# 001-0002_beaglebone_cape_board.net
KiCad netlist of a schematic drawn in Altium Designer
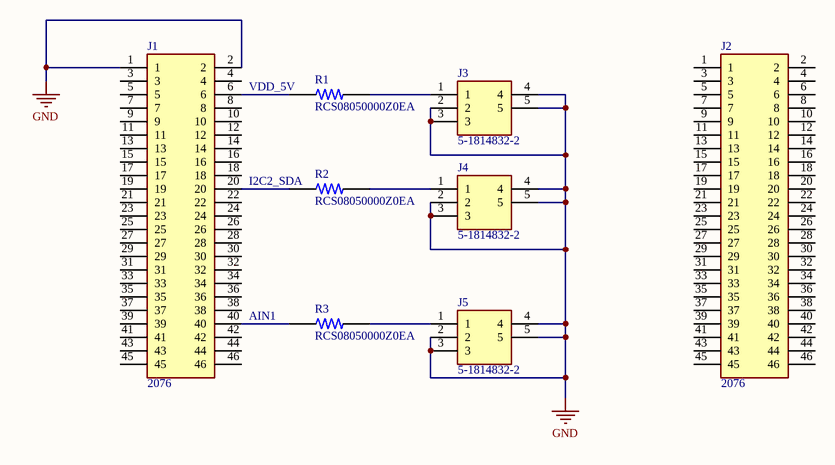
[diagram p0: 001-0002_beaglebone_cape_board.SchDoc]

(export (version "E")
  (design (tool "Eeschema 10.0.6"))
  (components
    (comp (ref "J1")
      (value "2076")
      (footprint "HDRV46W64P254_2X23_5842X500X874P")
      (description "Adafruit Accessories 2x23 Male Headers for BeagleBone Black - Two Pack")
      (fields (field (name "MOUSER PART NUMBER") "485-2076"))
      (libsource (lib "default") (part "2076"))
    )
    (comp (ref "J2")
      (value "2076")
      (footprint "HDRV46W64P254_2X23_5842X500X874P")
      (description "Adafruit Accessories 2x23 Male Headers for BeagleBone Black - Two Pack")
      (fields (field (name "MOUSER PART NUMBER") "485-2076"))
      (libsource (lib "default") (part "2076"))
    )
    (comp (ref "J3")
      (value "5-1814832-2")
      (footprint "5-1814832-2")
      (description "SMA Connector Jack, Female Socket 50 Ohms Through Hole Solder")
      (fields (field (name "MOUSER PART NUMBER") "571-5-1814832-2"))
      (libsource (lib "default") (part "5-1814832-2"))
    )
    (comp (ref "J4")
      (value "5-1814832-2")
      (footprint "5-1814832-2")
      (description "SMA Connector Jack, Female Socket 50 Ohms Through Hole Solder")
      (fields (field (name "MOUSER PART NUMBER") "571-5-1814832-2"))
      (libsource (lib "default") (part "5-1814832-2"))
    )
    (comp (ref "J5")
      (value "5-1814832-2")
      (footprint "5-1814832-2")
      (description "SMA Connector Jack, Female Socket 50 Ohms Through Hole Solder")
      (fields (field (name "MOUSER PART NUMBER") "571-5-1814832-2"))
      (libsource (lib "default") (part "5-1814832-2"))
    )
    (comp (ref "R1")
      (value "RCS08050000Z0EA")
      (footprint "default:RESC2012X50N")
      (description "RES SMD 0 OHM JUMPER 1/2W 0805")
      (fields (field (name "MF") "Vishay Dale") (field (name "DIGI-KEY_PART_NUMBER") "541-2827-1-ND"))
      (libsource (lib "default") (part "RCS08050000Z0EA"))
    )
    (comp (ref "R2")
      (value "RCS08050000Z0EA")
      (footprint "default:RESC2012X50N")
      (description "RES SMD 0 OHM JUMPER 1/2W 0805")
      (fields (field (name "MF") "Vishay Dale") (field (name "DIGI-KEY_PART_NUMBER") "541-2827-1-ND"))
      (libsource (lib "default") (part "RCS08050000Z0EA"))
    )
    (comp (ref "R3")
      (value "RCS08050000Z0EA")
      (footprint "default:RESC2012X50N")
      (description "RES SMD 0 OHM JUMPER 1/2W 0805")
      (fields (field (name "MF") "Vishay Dale") (field (name "DIGI-KEY_PART_NUMBER") "541-2827-1-ND"))
      (libsource (lib "default") (part "RCS08050000Z0EA"))
    )
  )
  (nets
    (net (code "1") (name "GND") (class "Default")
      (node (ref "J1") (pin "1") (pinfunction "1_1") (pintype "passive"))
      (node (ref "J1") (pin "2") (pinfunction "2_2") (pintype "passive"))
      (node (ref "J3") (pin "2") (pinfunction "2_2") (pintype "passive"))
      (node (ref "J3") (pin "3") (pinfunction "3_3") (pintype "passive"))
      (node (ref "J3") (pin "4") (pinfunction "4_4") (pintype "passive"))
      (node (ref "J3") (pin "5") (pinfunction "5_5") (pintype "passive"))
      (node (ref "J4") (pin "2") (pinfunction "2_2") (pintype "passive"))
      (node (ref "J4") (pin "3") (pinfunction "3_3") (pintype "passive"))
      (node (ref "J4") (pin "4") (pinfunction "4_4") (pintype "passive"))
      (node (ref "J4") (pin "5") (pinfunction "5_5") (pintype "passive"))
      (node (ref "J5") (pin "2") (pinfunction "2_2") (pintype "passive"))
      (node (ref "J5") (pin "3") (pinfunction "3_3") (pintype "passive"))
      (node (ref "J5") (pin "4") (pinfunction "4_4") (pintype "passive"))
      (node (ref "J5") (pin "5") (pinfunction "5_5") (pintype "passive"))
    )
    (net (code "2") (name "Net-(J1-Pad6)") (class "Default")
      (node (ref "J1") (pin "6") (pinfunction "6_6") (pintype "passive"))
      (node (ref "R1") (pin "1") (pinfunction "1_1") (pintype "passive"))
    )
    (net (code "3") (name "Net-(J1-Pad20)") (class "Default")
      (node (ref "J1") (pin "20") (pinfunction "20_20") (pintype "passive"))
      (node (ref "R2") (pin "1") (pinfunction "1_1") (pintype "passive"))
    )
    (net (code "4") (name "Net-(J1-Pad40)") (class "Default")
      (node (ref "J1") (pin "40") (pinfunction "40_40") (pintype "passive"))
      (node (ref "R3") (pin "1") (pinfunction "1_1") (pintype "passive"))
    )
    (net (code "5") (name "Net-(J3-Pad1)") (class "Default")
      (node (ref "J3") (pin "1") (pinfunction "1_1") (pintype "passive"))
      (node (ref "R1") (pin "2") (pinfunction "2_2") (pintype "passive"))
    )
    (net (code "6") (name "Net-(J4-Pad1)") (class "Default")
      (node (ref "J4") (pin "1") (pinfunction "1_1") (pintype "passive"))
      (node (ref "R2") (pin "2") (pinfunction "2_2") (pintype "passive"))
    )
    (net (code "7") (name "Net-(J5-Pad1)") (class "Default")
      (node (ref "J5") (pin "1") (pinfunction "1_1") (pintype "passive"))
      (node (ref "R3") (pin "2") (pinfunction "2_2") (pintype "passive"))
    )
    (net (code "8") (name "unconnected-(J1-Pad3)") (class "Default")
      (node (ref "J1") (pin "3") (pinfunction "3_3") (pintype "passive"))
    )
    (net (code "9") (name "unconnected-(J1-Pad4)") (class "Default")
      (node (ref "J1") (pin "4") (pinfunction "4_4") (pintype "passive"))
    )
    (net (code "10") (name "unconnected-(J1-Pad5)") (class "Default")
      (node (ref "J1") (pin "5") (pinfunction "5_5") (pintype "passive"))
    )
    (net (code "11") (name "unconnected-(J1-Pad7)") (class "Default")
      (node (ref "J1") (pin "7") (pinfunction "7_7") (pintype "passive"))
    )
    (net (code "12") (name "unconnected-(J1-Pad8)") (class "Default")
      (node (ref "J1") (pin "8") (pinfunction "8_8") (pintype "passive"))
    )
    (net (code "13") (name "unconnected-(J1-Pad9)") (class "Default")
      (node (ref "J1") (pin "9") (pinfunction "9_9") (pintype "passive"))
    )
    (net (code "14") (name "unconnected-(J1-Pad10)") (class "Default")
      (node (ref "J1") (pin "10") (pinfunction "10_10") (pintype "passive"))
    )
    (net (code "15") (name "unconnected-(J1-Pad11)") (class "Default")
      (node (ref "J1") (pin "11") (pinfunction "11_11") (pintype "passive"))
    )
    (net (code "16") (name "unconnected-(J1-Pad12)") (class "Default")
      (node (ref "J1") (pin "12") (pinfunction "12_12") (pintype "passive"))
    )
    (net (code "17") (name "unconnected-(J1-Pad13)") (class "Default")
      (node (ref "J1") (pin "13") (pinfunction "13_13") (pintype "passive"))
    )
    (net (code "18") (name "unconnected-(J1-Pad14)") (class "Default")
      (node (ref "J1") (pin "14") (pinfunction "14_14") (pintype "passive"))
    )
    (net (code "19") (name "unconnected-(J1-Pad15)") (class "Default")
      (node (ref "J1") (pin "15") (pinfunction "15_15") (pintype "passive"))
    )
    (net (code "20") (name "unconnected-(J1-Pad16)") (class "Default")
      (node (ref "J1") (pin "16") (pinfunction "16_16") (pintype "passive"))
    )
    (net (code "21") (name "unconnected-(J1-Pad17)") (class "Default")
      (node (ref "J1") (pin "17") (pinfunction "17_17") (pintype "passive"))
    )
    (net (code "22") (name "unconnected-(J1-Pad18)") (class "Default")
      (node (ref "J1") (pin "18") (pinfunction "18_18") (pintype "passive"))
    )
    (net (code "23") (name "unconnected-(J1-Pad19)") (class "Default")
      (node (ref "J1") (pin "19") (pinfunction "19_19") (pintype "passive"))
    )
    (net (code "24") (name "unconnected-(J1-Pad21)") (class "Default")
      (node (ref "J1") (pin "21") (pinfunction "21_21") (pintype "passive"))
    )
    (net (code "25") (name "unconnected-(J1-Pad22)") (class "Default")
      (node (ref "J1") (pin "22") (pinfunction "22_22") (pintype "passive"))
    )
    (net (code "26") (name "unconnected-(J1-Pad23)") (class "Default")
      (node (ref "J1") (pin "23") (pinfunction "23_23") (pintype "passive"))
    )
    (net (code "27") (name "unconnected-(J1-Pad24)") (class "Default")
      (node (ref "J1") (pin "24") (pinfunction "24_24") (pintype "passive"))
    )
    (net (code "28") (name "unconnected-(J1-Pad25)") (class "Default")
      (node (ref "J1") (pin "25") (pinfunction "25_25") (pintype "passive"))
    )
    (net (code "29") (name "unconnected-(J1-Pad26)") (class "Default")
      (node (ref "J1") (pin "26") (pinfunction "26_26") (pintype "passive"))
    )
    (net (code "30") (name "unconnected-(J1-Pad27)") (class "Default")
      (node (ref "J1") (pin "27") (pinfunction "27_27") (pintype "passive"))
    )
    (net (code "31") (name "unconnected-(J1-Pad28)") (class "Default")
      (node (ref "J1") (pin "28") (pinfunction "28_28") (pintype "passive"))
    )
    (net (code "32") (name "unconnected-(J1-Pad29)") (class "Default")
      (node (ref "J1") (pin "29") (pinfunction "29_29") (pintype "passive"))
    )
    (net (code "33") (name "unconnected-(J1-Pad30)") (class "Default")
      (node (ref "J1") (pin "30") (pinfunction "30_30") (pintype "passive"))
    )
    (net (code "34") (name "unconnected-(J1-Pad31)") (class "Default")
      (node (ref "J1") (pin "31") (pinfunction "31_31") (pintype "passive"))
    )
    (net (code "35") (name "unconnected-(J1-Pad32)") (class "Default")
      (node (ref "J1") (pin "32") (pinfunction "32_32") (pintype "passive"))
    )
    (net (code "36") (name "unconnected-(J1-Pad33)") (class "Default")
      (node (ref "J1") (pin "33") (pinfunction "33_33") (pintype "passive"))
    )
    (net (code "37") (name "unconnected-(J1-Pad34)") (class "Default")
      (node (ref "J1") (pin "34") (pinfunction "34_34") (pintype "passive"))
    )
    (net (code "38") (name "unconnected-(J1-Pad35)") (class "Default")
      (node (ref "J1") (pin "35") (pinfunction "35_35") (pintype "passive"))
    )
    (net (code "39") (name "unconnected-(J1-Pad36)") (class "Default")
      (node (ref "J1") (pin "36") (pinfunction "36_36") (pintype "passive"))
    )
    (net (code "40") (name "unconnected-(J1-Pad37)") (class "Default")
      (node (ref "J1") (pin "37") (pinfunction "37_37") (pintype "passive"))
    )
    (net (code "41") (name "unconnected-(J1-Pad38)") (class "Default")
      (node (ref "J1") (pin "38") (pinfunction "38_38") (pintype "passive"))
    )
    (net (code "42") (name "unconnected-(J1-Pad39)") (class "Default")
      (node (ref "J1") (pin "39") (pinfunction "39_39") (pintype "passive"))
    )
    (net (code "43") (name "unconnected-(J1-Pad41)") (class "Default")
      (node (ref "J1") (pin "41") (pinfunction "41_41") (pintype "passive"))
    )
    (net (code "44") (name "unconnected-(J1-Pad42)") (class "Default")
      (node (ref "J1") (pin "42") (pinfunction "42_42") (pintype "passive"))
    )
    (net (code "45") (name "unconnected-(J1-Pad43)") (class "Default")
      (node (ref "J1") (pin "43") (pinfunction "43_43") (pintype "passive"))
    )
    (net (code "46") (name "unconnected-(J1-Pad44)") (class "Default")
      (node (ref "J1") (pin "44") (pinfunction "44_44") (pintype "passive"))
    )
    (net (code "47") (name "unconnected-(J1-Pad45)") (class "Default")
      (node (ref "J1") (pin "45") (pinfunction "45_45") (pintype "passive"))
    )
    (net (code "48") (name "unconnected-(J1-Pad46)") (class "Default")
      (node (ref "J1") (pin "46") (pinfunction "46_46") (pintype "passive"))
    )
    (net (code "49") (name "unconnected-(J2-Pad1)") (class "Default")
      (node (ref "J2") (pin "1") (pinfunction "1_1") (pintype "passive"))
    )
    (net (code "50") (name "unconnected-(J2-Pad2)") (class "Default")
      (node (ref "J2") (pin "2") (pinfunction "2_2") (pintype "passive"))
    )
    (net (code "51") (name "unconnected-(J2-Pad3)") (class "Default")
      (node (ref "J2") (pin "3") (pinfunction "3_3") (pintype "passive"))
    )
    (net (code "52") (name "unconnected-(J2-Pad4)") (class "Default")
      (node (ref "J2") (pin "4") (pinfunction "4_4") (pintype "passive"))
    )
    (net (code "53") (name "unconnected-(J2-Pad5)") (class "Default")
      (node (ref "J2") (pin "5") (pinfunction "5_5") (pintype "passive"))
    )
    (net (code "54") (name "unconnected-(J2-Pad6)") (class "Default")
      (node (ref "J2") (pin "6") (pinfunction "6_6") (pintype "passive"))
    )
    (net (code "55") (name "unconnected-(J2-Pad7)") (class "Default")
      (node (ref "J2") (pin "7") (pinfunction "7_7") (pintype "passive"))
    )
    (net (code "56") (name "unconnected-(J2-Pad8)") (class "Default")
      (node (ref "J2") (pin "8") (pinfunction "8_8") (pintype "passive"))
    )
    (net (code "57") (name "unconnected-(J2-Pad9)") (class "Default")
      (node (ref "J2") (pin "9") (pinfunction "9_9") (pintype "passive"))
    )
    (net (code "58") (name "unconnected-(J2-Pad10)") (class "Default")
      (node (ref "J2") (pin "10") (pinfunction "10_10") (pintype "passive"))
    )
    (net (code "59") (name "unconnected-(J2-Pad11)") (class "Default")
      (node (ref "J2") (pin "11") (pinfunction "11_11") (pintype "passive"))
    )
    (net (code "60") (name "unconnected-(J2-Pad12)") (class "Default")
      (node (ref "J2") (pin "12") (pinfunction "12_12") (pintype "passive"))
    )
    (net (code "61") (name "unconnected-(J2-Pad13)") (class "Default")
      (node (ref "J2") (pin "13") (pinfunction "13_13") (pintype "passive"))
    )
    (net (code "62") (name "unconnected-(J2-Pad14)") (class "Default")
      (node (ref "J2") (pin "14") (pinfunction "14_14") (pintype "passive"))
    )
    (net (code "63") (name "unconnected-(J2-Pad15)") (class "Default")
      (node (ref "J2") (pin "15") (pinfunction "15_15") (pintype "passive"))
    )
    (net (code "64") (name "unconnected-(J2-Pad16)") (class "Default")
      (node (ref "J2") (pin "16") (pinfunction "16_16") (pintype "passive"))
    )
    (net (code "65") (name "unconnected-(J2-Pad17)") (class "Default")
      (node (ref "J2") (pin "17") (pinfunction "17_17") (pintype "passive"))
    )
    (net (code "66") (name "unconnected-(J2-Pad18)") (class "Default")
      (node (ref "J2") (pin "18") (pinfunction "18_18") (pintype "passive"))
    )
    (net (code "67") (name "unconnected-(J2-Pad19)") (class "Default")
      (node (ref "J2") (pin "19") (pinfunction "19_19") (pintype "passive"))
    )
    (net (code "68") (name "unconnected-(J2-Pad20)") (class "Default")
      (node (ref "J2") (pin "20") (pinfunction "20_20") (pintype "passive"))
    )
    (net (code "69") (name "unconnected-(J2-Pad21)") (class "Default")
      (node (ref "J2") (pin "21") (pinfunction "21_21") (pintype "passive"))
    )
    (net (code "70") (name "unconnected-(J2-Pad22)") (class "Default")
      (node (ref "J2") (pin "22") (pinfunction "22_22") (pintype "passive"))
    )
    (net (code "71") (name "unconnected-(J2-Pad23)") (class "Default")
      (node (ref "J2") (pin "23") (pinfunction "23_23") (pintype "passive"))
    )
    (net (code "72") (name "unconnected-(J2-Pad24)") (class "Default")
      (node (ref "J2") (pin "24") (pinfunction "24_24") (pintype "passive"))
    )
    (net (code "73") (name "unconnected-(J2-Pad25)") (class "Default")
      (node (ref "J2") (pin "25") (pinfunction "25_25") (pintype "passive"))
    )
    (net (code "74") (name "unconnected-(J2-Pad26)") (class "Default")
      (node (ref "J2") (pin "26") (pinfunction "26_26") (pintype "passive"))
    )
    (net (code "75") (name "unconnected-(J2-Pad27)") (class "Default")
      (node (ref "J2") (pin "27") (pinfunction "27_27") (pintype "passive"))
    )
    (net (code "76") (name "unconnected-(J2-Pad28)") (class "Default")
      (node (ref "J2") (pin "28") (pinfunction "28_28") (pintype "passive"))
    )
    (net (code "77") (name "unconnected-(J2-Pad29)") (class "Default")
      (node (ref "J2") (pin "29") (pinfunction "29_29") (pintype "passive"))
    )
    (net (code "78") (name "unconnected-(J2-Pad30)") (class "Default")
      (node (ref "J2") (pin "30") (pinfunction "30_30") (pintype "passive"))
    )
    (net (code "79") (name "unconnected-(J2-Pad31)") (class "Default")
      (node (ref "J2") (pin "31") (pinfunction "31_31") (pintype "passive"))
    )
    (net (code "80") (name "unconnected-(J2-Pad32)") (class "Default")
      (node (ref "J2") (pin "32") (pinfunction "32_32") (pintype "passive"))
    )
    (net (code "81") (name "unconnected-(J2-Pad33)") (class "Default")
      (node (ref "J2") (pin "33") (pinfunction "33_33") (pintype "passive"))
    )
    (net (code "82") (name "unconnected-(J2-Pad34)") (class "Default")
      (node (ref "J2") (pin "34") (pinfunction "34_34") (pintype "passive"))
    )
    (net (code "83") (name "unconnected-(J2-Pad35)") (class "Default")
      (node (ref "J2") (pin "35") (pinfunction "35_35") (pintype "passive"))
    )
    (net (code "84") (name "unconnected-(J2-Pad36)") (class "Default")
      (node (ref "J2") (pin "36") (pinfunction "36_36") (pintype "passive"))
    )
    (net (code "85") (name "unconnected-(J2-Pad37)") (class "Default")
      (node (ref "J2") (pin "37") (pinfunction "37_37") (pintype "passive"))
    )
    (net (code "86") (name "unconnected-(J2-Pad38)") (class "Default")
      (node (ref "J2") (pin "38") (pinfunction "38_38") (pintype "passive"))
    )
    (net (code "87") (name "unconnected-(J2-Pad39)") (class "Default")
      (node (ref "J2") (pin "39") (pinfunction "39_39") (pintype "passive"))
    )
    (net (code "88") (name "unconnected-(J2-Pad40)") (class "Default")
      (node (ref "J2") (pin "40") (pinfunction "40_40") (pintype "passive"))
    )
    (net (code "89") (name "unconnected-(J2-Pad41)") (class "Default")
      (node (ref "J2") (pin "41") (pinfunction "41_41") (pintype "passive"))
    )
    (net (code "90") (name "unconnected-(J2-Pad42)") (class "Default")
      (node (ref "J2") (pin "42") (pinfunction "42_42") (pintype "passive"))
    )
    (net (code "91") (name "unconnected-(J2-Pad43)") (class "Default")
      (node (ref "J2") (pin "43") (pinfunction "43_43") (pintype "passive"))
    )
    (net (code "92") (name "unconnected-(J2-Pad44)") (class "Default")
      (node (ref "J2") (pin "44") (pinfunction "44_44") (pintype "passive"))
    )
    (net (code "93") (name "unconnected-(J2-Pad45)") (class "Default")
      (node (ref "J2") (pin "45") (pinfunction "45_45") (pintype "passive"))
    )
    (net (code "94") (name "unconnected-(J2-Pad46)") (class "Default")
      (node (ref "J2") (pin "46") (pinfunction "46_46") (pintype "passive"))
    )
  )
)
